# XMC4800-ECAT-P0.net
KiCad netlist of a schematic drawn in Altium Designer
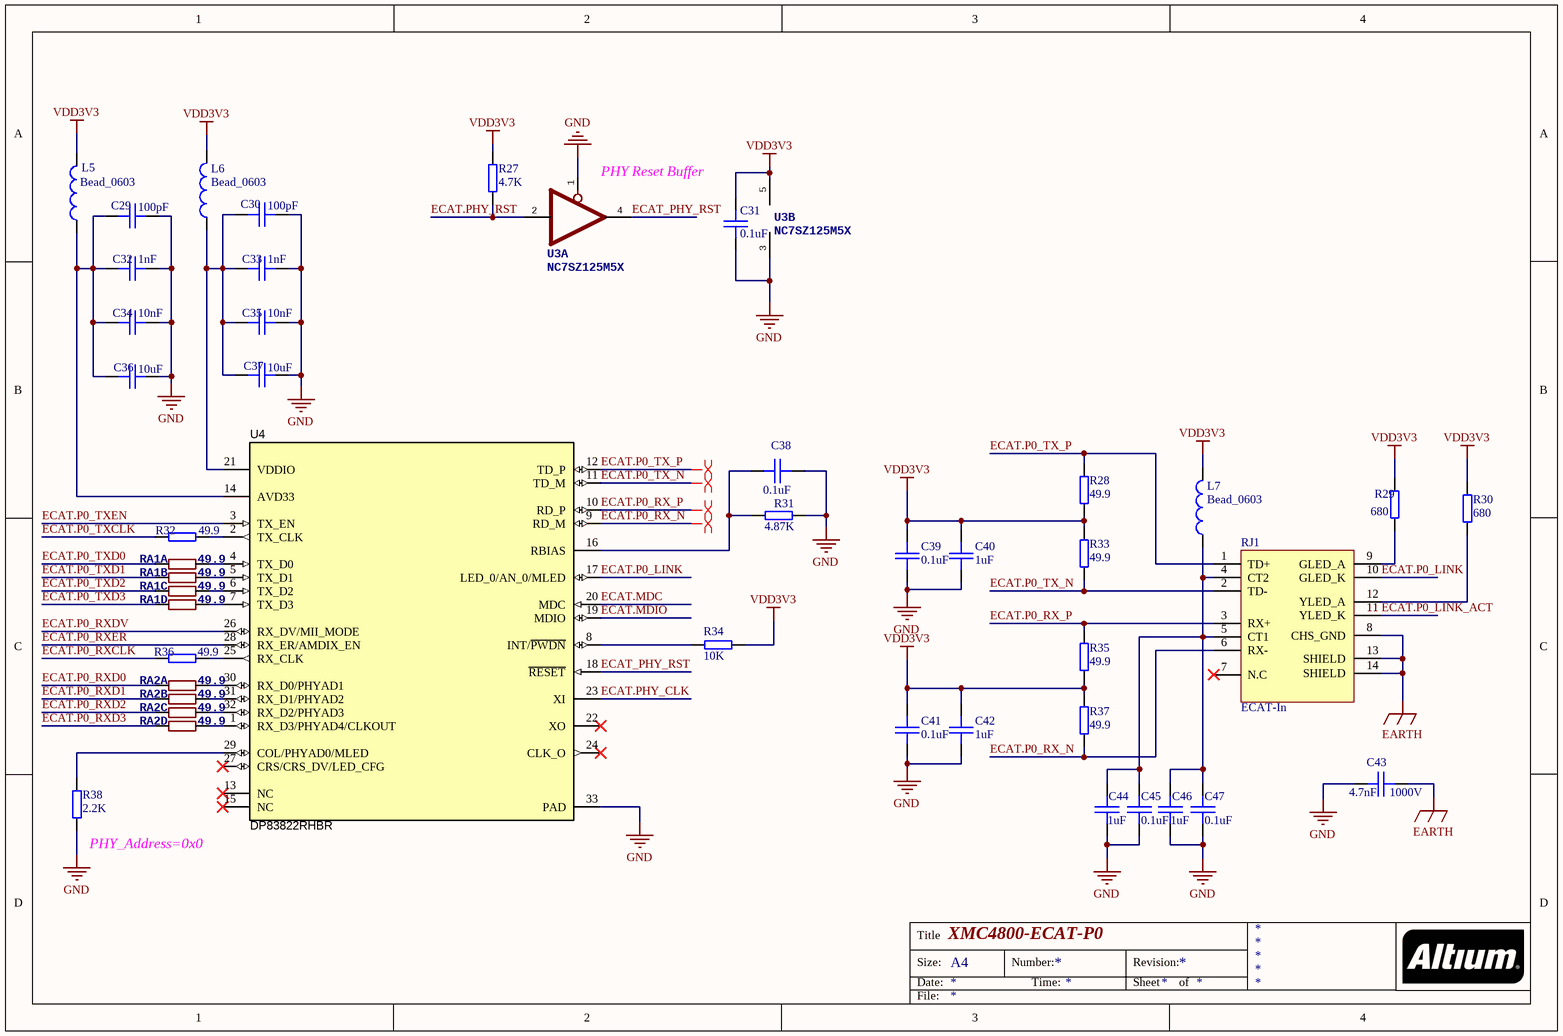
[diagram p0: XMC4800-ECAT-P0.SchDoc]

(export (version "E")
  (design (tool "Eeschema 10.0.6"))
  (components
    (comp (ref "C29")
      (value "100pF")
      (footprint "CAP-0603")
      (description "陶瓷贴片电容0603")
      (fields (field (name "TOLERANCE") "10%") (field (name "VOLTAGE") "50V"))
      (libsource (lib "momo") (part "C_0603"))
    )
    (comp (ref "C30")
      (value "100pF")
      (footprint "CAP-0603")
      (description "陶瓷贴片电容0603")
      (fields (field (name "TOLERANCE") "10%") (field (name "VOLTAGE") "50V"))
      (libsource (lib "momo") (part "C_0603"))
    )
    (comp (ref "C31")
      (value "0.1uF")
      (footprint "CAP-0603")
      (description "陶瓷贴片电容0603")
      (fields (field (name "TOLERANCE") "10%") (field (name "VOLTAGE") "50V"))
      (libsource (lib "momo") (part "C_0603"))
    )
    (comp (ref "C32")
      (value "1nF")
      (footprint "CAP-0603")
      (description "陶瓷贴片电容0603")
      (fields (field (name "TOLERANCE") "10%") (field (name "VOLTAGE") "50V"))
      (libsource (lib "momo") (part "C_0603"))
    )
    (comp (ref "C33")
      (value "1nF")
      (footprint "CAP-0603")
      (description "陶瓷贴片电容0603")
      (fields (field (name "TOLERANCE") "10%") (field (name "VOLTAGE") "50V"))
      (libsource (lib "momo") (part "C_0603"))
    )
    (comp (ref "C34")
      (value "10nF")
      (footprint "CAP-0603")
      (description "陶瓷贴片电容0603")
      (fields (field (name "TOLERANCE") "10%") (field (name "VOLTAGE") "50V"))
      (libsource (lib "momo") (part "C_0603"))
    )
    (comp (ref "C35")
      (value "10nF")
      (footprint "CAP-0603")
      (description "陶瓷贴片电容0603")
      (fields (field (name "TOLERANCE") "10%") (field (name "VOLTAGE") "50V"))
      (libsource (lib "momo") (part "C_0603"))
    )
    (comp (ref "C36")
      (value "10uF")
      (footprint "CAP-0603")
      (description "陶瓷贴片电容0603")
      (fields (field (name "TOLERANCE") "10%") (field (name "VOLTAGE") "50V"))
      (libsource (lib "momo") (part "C_0603"))
    )
    (comp (ref "C37")
      (value "10uF")
      (footprint "CAP-0603")
      (description "陶瓷贴片电容0603")
      (fields (field (name "TOLERANCE") "10%") (field (name "VOLTAGE") "50V"))
      (libsource (lib "momo") (part "C_0603"))
    )
    (comp (ref "C38")
      (value "0.1uF")
      (footprint "CAP-0603")
      (description "陶瓷贴片电容0603")
      (fields (field (name "TOLERANCE") "10%") (field (name "VOLTAGE") "50V"))
      (libsource (lib "momo") (part "C_0603"))
    )
    (comp (ref "C39")
      (value "0.1uF")
      (footprint "CAP-0603")
      (description "陶瓷贴片电容0603")
      (fields (field (name "TOLERANCE") "10%") (field (name "VOLTAGE") "50V"))
      (libsource (lib "momo") (part "C_0603"))
    )
    (comp (ref "C40")
      (value "1uF")
      (footprint "CAP-0603")
      (description "陶瓷贴片电容0603")
      (fields (field (name "TOLERANCE") "10%") (field (name "VOLTAGE") "50V"))
      (libsource (lib "momo") (part "C_0603"))
    )
    (comp (ref "C41")
      (value "0.1uF")
      (footprint "CAP-0603")
      (description "陶瓷贴片电容0603")
      (fields (field (name "TOLERANCE") "10%") (field (name "VOLTAGE") "50V"))
      (libsource (lib "momo") (part "C_0603"))
    )
    (comp (ref "C42")
      (value "1uF")
      (footprint "CAP-0603")
      (description "陶瓷贴片电容0603")
      (fields (field (name "TOLERANCE") "10%") (field (name "VOLTAGE") "50V"))
      (libsource (lib "momo") (part "C_0603"))
    )
    (comp (ref "C43")
      (value "4.7nF")
      (footprint "CAP-1206")
      (description "陶瓷贴片电容1206")
      (fields (field (name "TOLERANCE") "10%") (field (name "VOLTAGE") "1000V"))
      (libsource (lib "momo") (part "C_1206"))
    )
    (comp (ref "C44")
      (value "1uF")
      (footprint "CAP-0603")
      (description "陶瓷贴片电容0603")
      (fields (field (name "TOLERANCE") "10%") (field (name "VOLTAGE") "50V"))
      (libsource (lib "momo") (part "C_0603"))
    )
    (comp (ref "C45")
      (value "0.1uF")
      (footprint "CAP-0603")
      (description "陶瓷贴片电容0603")
      (fields (field (name "TOLERANCE") "10%") (field (name "VOLTAGE") "50V"))
      (libsource (lib "momo") (part "C_0603"))
    )
    (comp (ref "C46")
      (value "1uF")
      (footprint "CAP-0603")
      (description "陶瓷贴片电容0603")
      (fields (field (name "TOLERANCE") "10%") (field (name "VOLTAGE") "50V"))
      (libsource (lib "momo") (part "C_0603"))
    )
    (comp (ref "C47")
      (value "0.1uF")
      (footprint "CAP-0603")
      (description "陶瓷贴片电容0603")
      (fields (field (name "TOLERANCE") "10%") (field (name "VOLTAGE") "50V"))
      (libsource (lib "momo") (part "C_0603"))
    )
    (comp (ref "L5")
      (value "Bead_0603")
      (footprint "L-0603")
      (description "贴片磁珠0603")
      (libsource (lib "momo") (part "Bead_0603"))
    )
    (comp (ref "L6")
      (value "Bead_0603")
      (footprint "L-0603")
      (description "贴片磁珠0603")
      (libsource (lib "momo") (part "Bead_0603"))
    )
    (comp (ref "L7")
      (value "Bead_0603")
      (footprint "L-0603")
      (description "贴片磁珠0603")
      (libsource (lib "momo") (part "Bead_0603"))
    )
    (comp (ref "R27")
      (value "4.7K")
      (footprint "RES-0603")
      (description "贴片电阻0603")
      (fields (field (name "TOLERANCE") "5%") (field (name "VOLTAGE") "50V"))
      (libsource (lib "momo") (part "R_0603"))
    )
    (comp (ref "R28")
      (value "49.9")
      (footprint "RES-0603")
      (description "贴片电阻0603")
      (fields (field (name "TOLERANCE") "5%") (field (name "VOLTAGE") "50V"))
      (libsource (lib "momo") (part "R_0603"))
    )
    (comp (ref "R29")
      (value "680")
      (footprint "RES-0603")
      (description "贴片电阻0603")
      (fields (field (name "TOLERANCE") "5%") (field (name "VOLTAGE") "50V"))
      (libsource (lib "momo") (part "R_0603"))
    )
    (comp (ref "R30")
      (value "680")
      (footprint "RES-0603")
      (description "贴片电阻0603")
      (fields (field (name "TOLERANCE") "5%") (field (name "VOLTAGE") "50V"))
      (libsource (lib "momo") (part "R_0603"))
    )
    (comp (ref "R31")
      (value "4.87K")
      (footprint "RES-0603")
      (description "贴片电阻0603")
      (fields (field (name "TOLERANCE") "5%") (field (name "VOLTAGE") "50V"))
      (libsource (lib "momo") (part "R_0603"))
    )
    (comp (ref "R32")
      (value "49.9")
      (footprint "RES-0603")
      (description "贴片电阻0603")
      (fields (field (name "TOLERANCE") "5%") (field (name "VOLTAGE") "50V"))
      (libsource (lib "momo") (part "R_0603"))
    )
    (comp (ref "R33")
      (value "49.9")
      (footprint "RES-0603")
      (description "贴片电阻0603")
      (fields (field (name "TOLERANCE") "5%") (field (name "VOLTAGE") "50V"))
      (libsource (lib "momo") (part "R_0603"))
    )
    (comp (ref "R34")
      (value "10K")
      (footprint "RES-0603")
      (description "贴片电阻0603")
      (fields (field (name "TOLERANCE") "5%") (field (name "VOLTAGE") "50V"))
      (libsource (lib "momo") (part "R_0603"))
    )
    (comp (ref "R35")
      (value "49.9")
      (footprint "RES-0603")
      (description "贴片电阻0603")
      (fields (field (name "TOLERANCE") "5%") (field (name "VOLTAGE") "50V"))
      (libsource (lib "momo") (part "R_0603"))
    )
    (comp (ref "R36")
      (value "49.9")
      (footprint "RES-0603")
      (description "贴片电阻0603")
      (fields (field (name "TOLERANCE") "5%") (field (name "VOLTAGE") "50V"))
      (libsource (lib "momo") (part "R_0603"))
    )
    (comp (ref "R37")
      (value "49.9")
      (footprint "RES-0603")
      (description "贴片电阻0603")
      (fields (field (name "TOLERANCE") "5%") (field (name "VOLTAGE") "50V"))
      (libsource (lib "momo") (part "R_0603"))
    )
    (comp (ref "R38")
      (value "2.2K")
      (footprint "RES-0603")
      (description "贴片电阻0603")
      (fields (field (name "TOLERANCE") "5%") (field (name "VOLTAGE") "50V"))
      (libsource (lib "momo") (part "R_0603"))
    )
    (comp (ref "RA1")
      (value "49.9")
      (footprint "LC-0603_Rx4")
      (description "排阻")
      (libsource (lib "momo") (part "RS_ARR4"))
    )
    (comp (ref "RA2")
      (value "49.9")
      (footprint "LC-0603_Rx4")
      (description "排阻")
      (libsource (lib "momo") (part "RS_ARR4"))
    )
    (comp (ref "RJ1")
      (value "ECAT-In")
      (footprint "momo:HR911105A")
      (description "Input")
      (fields (field (name "PUBLISHER") "Altium Limited"))
      (libsource (lib "momo") (part "HR911105A"))
    )
    (comp (ref "U3")
      (value "NC7SZ125M5X")
      (footprint "LC-SOT-23-5")
      (description "单通道缓冲器，3态输出")
      (libsource (lib "momo") (part "NC7SZ125M5X"))
    )
    (comp (ref "U4")
      (value "DP83822RHBR")
      (footprint "RHB0032B")
      (description "10/100 Ethernet PHY, RHB0032B")
      (fields
        (field (name "ALTERNATE PARTNUMBER") "DP83822RHBT")
        (field (name "MANUFACTURER") "Texas Instruments")
        (field (name "SYMBOLCREATOR") "Altium")
        (field (name "PUBLISHER") "Texas Instruments")
      )
      (libsource (lib "momo") (part "DP83822RHBR"))
    )
  )
  (nets
    (net (code "1") (name "/ECAT.MDC") (class "Default")
      (node (ref "U4") (pin "20") (pinfunction "MDC_20") (pintype "input"))
    )
    (net (code "2") (name "/ECAT.MDIO") (class "Default")
      (node (ref "U4") (pin "19") (pinfunction "MDIO_19") (pintype "bidirectional"))
    )
    (net (code "3") (name "/ECAT.P0_LINK") (class "Default")
      (node (ref "RJ1") (pin "10") (pinfunction "GLED_K_10") (pintype "passive"))
      (node (ref "U4") (pin "17") (pinfunction "LED_0/AN_0/MLED_17") (pintype "bidirectional"))
    )
    (net (code "4") (name "/ECAT.P0_LINK_ACT") (class "Default")
      (node (ref "RJ1") (pin "11") (pinfunction "YLED_K_11") (pintype "passive"))
    )
    (net (code "5") (name "/ECAT.P0_RXCLK") (class "Default")
      (node (ref "R36") (pin "1") (pinfunction "1_1") (pintype "passive"))
    )
    (net (code "6") (name "/ECAT.P0_RXD0") (class "Default")
      (node (ref "RA2") (pin "1") (pinfunction "1_1") (pintype "passive"))
    )
    (net (code "7") (name "/ECAT.P0_RXD1") (class "Default")
      (node (ref "RA2") (pin "2") (pinfunction "1_2") (pintype "passive"))
    )
    (net (code "8") (name "/ECAT.P0_RXD2") (class "Default")
      (node (ref "RA2") (pin "3") (pinfunction "1_3") (pintype "passive"))
    )
    (net (code "9") (name "/ECAT.P0_RXD3") (class "Default")
      (node (ref "RA2") (pin "4") (pinfunction "1_4") (pintype "passive"))
    )
    (net (code "10") (name "/ECAT.P0_RXDV") (class "Default")
      (node (ref "U4") (pin "26") (pinfunction "RX_DV/MII_MODE_26") (pintype "bidirectional"))
    )
    (net (code "11") (name "/ECAT.P0_RXER") (class "Default")
      (node (ref "U4") (pin "28") (pinfunction "RX_ER/AMDIX_EN_28") (pintype "bidirectional"))
    )
    (net (code "12") (name "/ECAT.P0_RX_N") (class "Default")
      (node (ref "R37") (pin "1") (pinfunction "1_1") (pintype "passive"))
      (node (ref "RJ1") (pin "6") (pinfunction "RX-_6") (pintype "passive"))
      (node (ref "U4") (pin "9") (pinfunction "RD_M_9") (pintype "bidirectional"))
    )
    (net (code "13") (name "/ECAT.P0_RX_P") (class "Default")
      (node (ref "R35") (pin "2") (pinfunction "2_2") (pintype "passive"))
      (node (ref "RJ1") (pin "3") (pinfunction "RX+_3") (pintype "passive"))
      (node (ref "U4") (pin "10") (pinfunction "RD_P_10") (pintype "bidirectional"))
    )
    (net (code "14") (name "/ECAT.P0_TXCLK") (class "Default")
      (node (ref "R32") (pin "1") (pinfunction "1_1") (pintype "passive"))
    )
    (net (code "15") (name "/ECAT.P0_TXD0") (class "Default")
      (node (ref "RA1") (pin "1") (pinfunction "1_1") (pintype "passive"))
    )
    (net (code "16") (name "/ECAT.P0_TXD1") (class "Default")
      (node (ref "RA1") (pin "2") (pinfunction "1_2") (pintype "passive"))
    )
    (net (code "17") (name "/ECAT.P0_TXD2") (class "Default")
      (node (ref "RA1") (pin "3") (pinfunction "1_3") (pintype "passive"))
    )
    (net (code "18") (name "/ECAT.P0_TXD3") (class "Default")
      (node (ref "RA1") (pin "4") (pinfunction "1_4") (pintype "passive"))
    )
    (net (code "19") (name "/ECAT.P0_TXEN") (class "Default")
      (node (ref "U4") (pin "3") (pinfunction "TX_EN_3") (pintype "input"))
    )
    (net (code "20") (name "/ECAT.P0_TX_N") (class "Default")
      (node (ref "R33") (pin "1") (pinfunction "1_1") (pintype "passive"))
      (node (ref "RJ1") (pin "2") (pinfunction "TD-_2") (pintype "passive"))
      (node (ref "U4") (pin "11") (pinfunction "TD_M_11") (pintype "bidirectional"))
    )
    (net (code "21") (name "/ECAT.P0_TX_P") (class "Default")
      (node (ref "R28") (pin "2") (pinfunction "2_2") (pintype "passive"))
      (node (ref "RJ1") (pin "1") (pinfunction "TD+_1") (pintype "passive"))
      (node (ref "U4") (pin "12") (pinfunction "TD_P_12") (pintype "bidirectional"))
    )
    (net (code "22") (name "/ECAT.PHY_CLK") (class "Default")
      (node (ref "U4") (pin "23") (pinfunction "XI_23") (pintype "passive"))
    )
    (net (code "23") (name "/ECAT.PHY_RST") (class "Default")
      (node (ref "R27") (pin "1") (pinfunction "1_1") (pintype "passive"))
      (node (ref "U3") (pin "2") (pinfunction "I_2") (pintype "passive"))
    )
    (net (code "24") (name "/ECAT_PHY_RST") (class "Default")
      (node (ref "U3") (pin "4") (pinfunction "O_4") (pintype "tri_state"))
      (node (ref "U4") (pin "18") (pinfunction "RESET_18") (pintype "input"))
    )
    (net (code "25") (name "EARTH") (class "Default")
      (node (ref "C43") (pin "2") (pinfunction "2_2") (pintype "passive"))
      (node (ref "RJ1") (pin "13") (pinfunction "SHIELD_13") (pintype "power_in"))
      (node (ref "RJ1") (pin "14") (pinfunction "SHIELD_14") (pintype "power_in"))
      (node (ref "RJ1") (pin "8") (pinfunction "CHS_GND_8") (pintype "passive"))
    )
    (net (code "26") (name "GND") (class "Default")
      (node (ref "C29") (pin "2") (pinfunction "2_2") (pintype "passive"))
      (node (ref "C30") (pin "2") (pinfunction "2_2") (pintype "passive"))
      (node (ref "C31") (pin "2") (pinfunction "2_2") (pintype "passive"))
      (node (ref "C32") (pin "1") (pinfunction "1_1") (pintype "passive"))
      (node (ref "C33") (pin "1") (pinfunction "1_1") (pintype "passive"))
      (node (ref "C34") (pin "1") (pinfunction "1_1") (pintype "passive"))
      (node (ref "C35") (pin "1") (pinfunction "1_1") (pintype "passive"))
      (node (ref "C36") (pin "1") (pinfunction "1_1") (pintype "passive"))
      (node (ref "C37") (pin "1") (pinfunction "1_1") (pintype "passive"))
      (node (ref "C38") (pin "2") (pinfunction "2_2") (pintype "passive"))
      (node (ref "C39") (pin "2") (pinfunction "2_2") (pintype "passive"))
      (node (ref "C40") (pin "2") (pinfunction "2_2") (pintype "passive"))
      (node (ref "C41") (pin "2") (pinfunction "2_2") (pintype "passive"))
      (node (ref "C42") (pin "2") (pinfunction "2_2") (pintype "passive"))
      (node (ref "C43") (pin "1") (pinfunction "1_1") (pintype "passive"))
      (node (ref "C44") (pin "2") (pinfunction "2_2") (pintype "passive"))
      (node (ref "C45") (pin "2") (pinfunction "2_2") (pintype "passive"))
      (node (ref "C46") (pin "2") (pinfunction "2_2") (pintype "passive"))
      (node (ref "C47") (pin "2") (pinfunction "2_2") (pintype "passive"))
      (node (ref "R31") (pin "2") (pinfunction "2_2") (pintype "passive"))
      (node (ref "R38") (pin "1") (pinfunction "1_1") (pintype "passive"))
      (node (ref "U3") (pin "1") (pinfunction "OE_1") (pintype "passive"))
      (node (ref "U3") (pin "3") (pinfunction "GND_3") (pintype "power_in"))
      (node (ref "U4") (pin "33") (pinfunction "PAD_33") (pintype "power_in"))
    )
    (net (code "27") (name "Net-(RA1A-2)") (class "Default")
      (node (ref "RA1") (pin "8") (pinfunction "2_8") (pintype "passive"))
      (node (ref "U4") (pin "4") (pinfunction "TX_D0_4") (pintype "input"))
    )
    (net (code "28") (name "Net-(RA1B-2)") (class "Default")
      (node (ref "RA1") (pin "7") (pinfunction "2_7") (pintype "passive"))
      (node (ref "U4") (pin "5") (pinfunction "TX_D1_5") (pintype "input"))
    )
    (net (code "29") (name "Net-(RA1C-2)") (class "Default")
      (node (ref "RA1") (pin "6") (pinfunction "2_6") (pintype "passive"))
      (node (ref "U4") (pin "6") (pinfunction "TX_D2_6") (pintype "input"))
    )
    (net (code "30") (name "Net-(RA1D-2)") (class "Default")
      (node (ref "RA1") (pin "5") (pinfunction "2_5") (pintype "passive"))
      (node (ref "U4") (pin "7") (pinfunction "TX_D3_7") (pintype "input"))
    )
    (net (code "31") (name "Net-(RA2A-2)") (class "Default")
      (node (ref "RA2") (pin "8") (pinfunction "2_8") (pintype "passive"))
      (node (ref "U4") (pin "30") (pinfunction "RX_D0/PHYAD1_30") (pintype "bidirectional"))
    )
    (net (code "32") (name "Net-(RA2B-2)") (class "Default")
      (node (ref "RA2") (pin "7") (pinfunction "2_7") (pintype "passive"))
      (node (ref "U4") (pin "31") (pinfunction "RX_D1/PHYAD2_31") (pintype "bidirectional"))
    )
    (net (code "33") (name "Net-(RA2C-2)") (class "Default")
      (node (ref "RA2") (pin "6") (pinfunction "2_6") (pintype "passive"))
      (node (ref "U4") (pin "32") (pinfunction "RX_D2/PHYAD3_32") (pintype "bidirectional"))
    )
    (net (code "34") (name "Net-(RA2D-2)") (class "Default")
      (node (ref "RA2") (pin "5") (pinfunction "2_5") (pintype "passive"))
      (node (ref "U4") (pin "1") (pinfunction "RX_D3/PHYAD4/CLKOUT_1") (pintype "bidirectional"))
    )
    (net (code "35") (name "Net-(RJ1-CT1)") (class "Default")
      (node (ref "C44") (pin "1") (pinfunction "1_1") (pintype "passive"))
      (node (ref "C45") (pin "1") (pinfunction "1_1") (pintype "passive"))
      (node (ref "C46") (pin "1") (pinfunction "1_1") (pintype "passive"))
      (node (ref "C47") (pin "1") (pinfunction "1_1") (pintype "passive"))
      (node (ref "L7") (pin "1") (pinfunction "1_1") (pintype "passive"))
      (node (ref "RJ1") (pin "4") (pinfunction "CT2_4") (pintype "passive"))
      (node (ref "RJ1") (pin "5") (pinfunction "CT1_5") (pintype "passive"))
    )
    (net (code "36") (name "Net-(RJ1-GLED_A)") (class "Default")
      (node (ref "R29") (pin "1") (pinfunction "1_1") (pintype "passive"))
      (node (ref "RJ1") (pin "9") (pinfunction "GLED_A_9") (pintype "passive"))
    )
    (net (code "37") (name "Net-(RJ1-YLED_A)") (class "Default")
      (node (ref "R30") (pin "2") (pinfunction "2_2") (pintype "passive"))
      (node (ref "RJ1") (pin "12") (pinfunction "YLED_A_12") (pintype "passive"))
    )
    (net (code "38") (name "Net-(U4-AVD33)") (class "Default")
      (node (ref "C29") (pin "1") (pinfunction "1_1") (pintype "passive"))
      (node (ref "C32") (pin "2") (pinfunction "2_2") (pintype "passive"))
      (node (ref "C34") (pin "2") (pinfunction "2_2") (pintype "passive"))
      (node (ref "C36") (pin "2") (pinfunction "2_2") (pintype "passive"))
      (node (ref "L5") (pin "1") (pinfunction "1_1") (pintype "passive"))
      (node (ref "U4") (pin "14") (pinfunction "AVD33_14") (pintype "power_in"))
    )
    (net (code "39") (name "Net-(U4-COL{slash}PHYAD0{slash}MLED)") (class "Default")
      (node (ref "R38") (pin "2") (pinfunction "2_2") (pintype "passive"))
      (node (ref "U4") (pin "29") (pinfunction "COL/PHYAD0/MLED_29") (pintype "bidirectional"))
    )
    (net (code "40") (name "Net-(U4-INT{slash}~{PWDN})") (class "Default")
      (node (ref "R34") (pin "1") (pinfunction "1_1") (pintype "passive"))
      (node (ref "U4") (pin "8") (pinfunction "INT/~{PWDN}_8") (pintype "bidirectional"))
    )
    (net (code "41") (name "Net-(U4-RBIAS)") (class "Default")
      (node (ref "C38") (pin "1") (pinfunction "1_1") (pintype "passive"))
      (node (ref "R31") (pin "1") (pinfunction "1_1") (pintype "passive"))
      (node (ref "U4") (pin "16") (pinfunction "RBIAS_16") (pintype "passive"))
    )
    (net (code "42") (name "Net-(U4-RX_CLK)") (class "Default")
      (node (ref "R36") (pin "2") (pinfunction "2_2") (pintype "passive"))
      (node (ref "U4") (pin "25") (pinfunction "RX_CLK_25") (pintype "output"))
    )
    (net (code "43") (name "Net-(U4-TX_CLK)") (class "Default")
      (node (ref "R32") (pin "2") (pinfunction "2_2") (pintype "passive"))
      (node (ref "U4") (pin "2") (pinfunction "TX_CLK_2") (pintype "output"))
    )
    (net (code "44") (name "Net-(U4-VDDIO)") (class "Default")
      (node (ref "C30") (pin "1") (pinfunction "1_1") (pintype "passive"))
      (node (ref "C33") (pin "2") (pinfunction "2_2") (pintype "passive"))
      (node (ref "C35") (pin "2") (pinfunction "2_2") (pintype "passive"))
      (node (ref "C37") (pin "2") (pinfunction "2_2") (pintype "passive"))
      (node (ref "L6") (pin "1") (pinfunction "1_1") (pintype "passive"))
      (node (ref "U4") (pin "21") (pinfunction "VDDIO_21") (pintype "power_in"))
    )
    (net (code "45") (name "VDD3V3") (class "Default")
      (node (ref "C31") (pin "1") (pinfunction "1_1") (pintype "passive"))
      (node (ref "C39") (pin "1") (pinfunction "1_1") (pintype "passive"))
      (node (ref "C40") (pin "1") (pinfunction "1_1") (pintype "passive"))
      (node (ref "C41") (pin "1") (pinfunction "1_1") (pintype "passive"))
      (node (ref "C42") (pin "1") (pinfunction "1_1") (pintype "passive"))
      (node (ref "L5") (pin "2") (pinfunction "2_2") (pintype "passive"))
      (node (ref "L6") (pin "2") (pinfunction "2_2") (pintype "passive"))
      (node (ref "L7") (pin "2") (pinfunction "2_2") (pintype "passive"))
      (node (ref "R27") (pin "2") (pinfunction "2_2") (pintype "passive"))
      (node (ref "R28") (pin "1") (pinfunction "1_1") (pintype "passive"))
      (node (ref "R29") (pin "2") (pinfunction "2_2") (pintype "passive"))
      (node (ref "R30") (pin "1") (pinfunction "1_1") (pintype "passive"))
      (node (ref "R33") (pin "2") (pinfunction "2_2") (pintype "passive"))
      (node (ref "R34") (pin "2") (pinfunction "2_2") (pintype "passive"))
      (node (ref "R35") (pin "1") (pinfunction "1_1") (pintype "passive"))
      (node (ref "R37") (pin "2") (pinfunction "2_2") (pintype "passive"))
      (node (ref "U3") (pin "5") (pinfunction "VDD_5") (pintype "power_in"))
    )
    (net (code "46") (name "unconnected-(RJ1-N.C-Pad7)") (class "Default")
      (node (ref "RJ1") (pin "7") (pinfunction "N.C_7") (pintype "passive+no_connect"))
    )
    (net (code "47") (name "unconnected-(U4-CLK_O-Pad24)") (class "Default")
      (node (ref "U4") (pin "24") (pinfunction "CLK_O_24") (pintype "output+no_connect"))
    )
    (net (code "48") (name "unconnected-(U4-CRS{slash}CRS_DV{slash}LED_CFG-Pad27)") (class "Default")
      (node (ref "U4") (pin "27") (pinfunction "CRS/CRS_DV/LED_CFG_27") (pintype "bidirectional+no_connect"))
    )
    (net (code "49") (name "unconnected-(U4-NC-Pad13)") (class "Default")
      (node (ref "U4") (pin "13") (pinfunction "NC_13") (pintype "passive+no_connect"))
    )
    (net (code "50") (name "unconnected-(U4-NC-Pad15)") (class "Default")
      (node (ref "U4") (pin "15") (pinfunction "NC_15") (pintype "passive+no_connect"))
    )
    (net (code "51") (name "unconnected-(U4-XO-Pad22)") (class "Default")
      (node (ref "U4") (pin "22") (pinfunction "XO_22") (pintype "passive+no_connect"))
    )
  )
)
